# PH_074_isolated_SMD.net
KiCad netlist of a schematic drawn in EAGLE
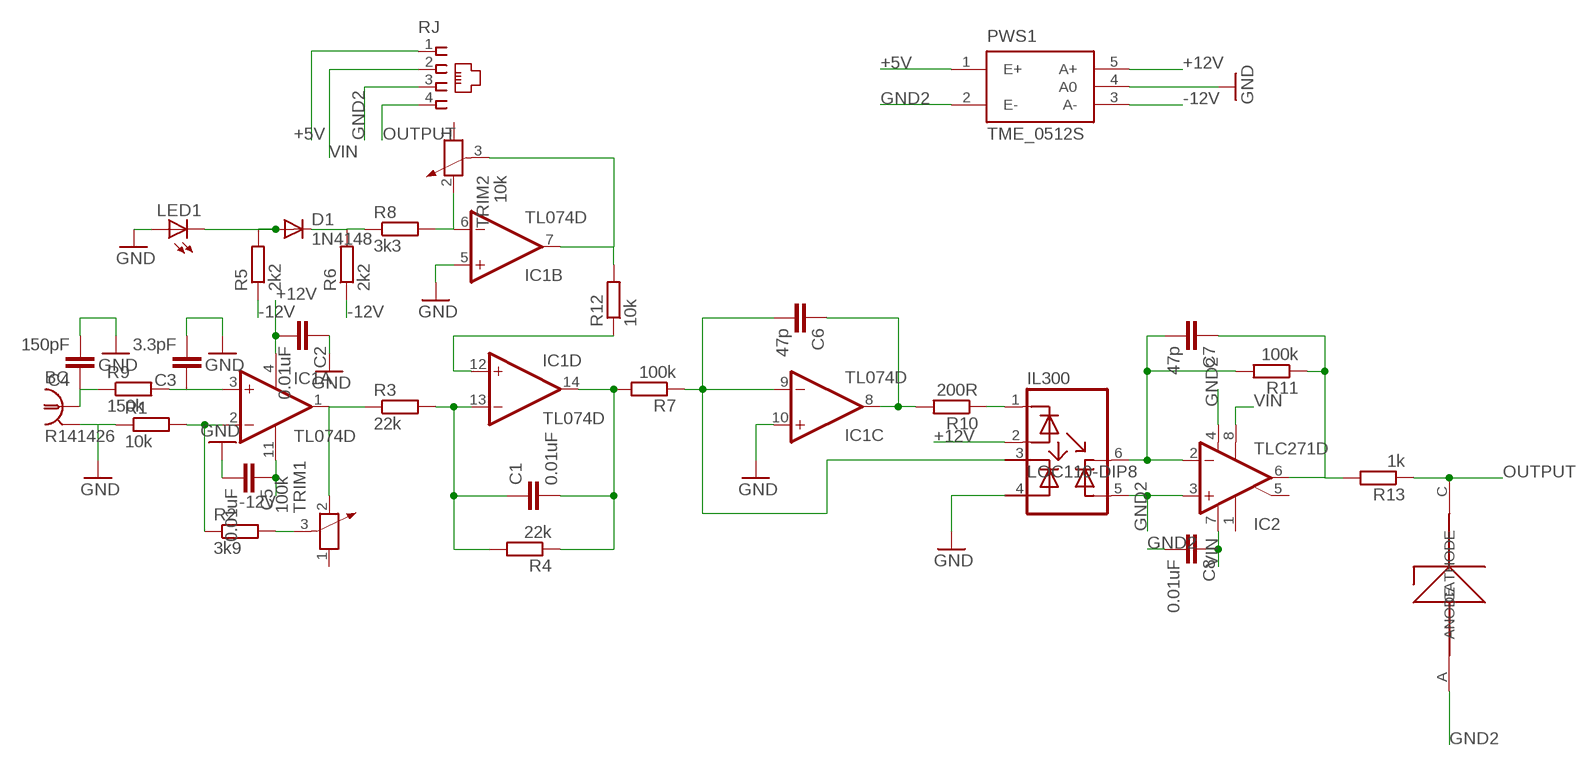
[diagram p0: schematic, sheet 1]

(export (version "E")
  (design (tool "Eeschema 10.0.6"))
  (components
    (comp (ref "BC")
      (value "R141426")
      (footprint "eagle-import:R141426")
      (fields (field (name "MF") "FARNELL") (field (name "MPN") "R141426161"))
      (libsource (lib "eagle-import") (part "R141426"))
    )
    (comp (ref "C1")
      (value "0.01uF")
      (footprint "eagle-import:C1206")
      (libsource (lib "eagle-import") (part "C-EUC1206"))
    )
    (comp (ref "C2")
      (value "0.01uF")
      (footprint "eagle-import:C1206")
      (libsource (lib "eagle-import") (part "C-EUC1206"))
    )
    (comp (ref "C3")
      (value "3.3pF")
      (footprint "eagle-import:C0805")
      (libsource (lib "eagle-import") (part "C-EUC0805"))
    )
    (comp (ref "C4")
      (value "150pF")
      (footprint "eagle-import:C0805")
      (libsource (lib "eagle-import") (part "C-EUC0805"))
    )
    (comp (ref "C5")
      (value "0.01uF")
      (footprint "eagle-import:C0805")
      (libsource (lib "eagle-import") (part "C-EUC0805"))
    )
    (comp (ref "C6")
      (value "47p")
      (footprint "eagle-import:C0805")
      (libsource (lib "eagle-import") (part "C-EUC0805"))
    )
    (comp (ref "C7")
      (value "47p")
      (footprint "eagle-import:C1206")
      (libsource (lib "eagle-import") (part "C-EUC1206"))
    )
    (comp (ref "C8")
      (value "0.01uF")
      (footprint "eagle-import:C0805")
      (libsource (lib "eagle-import") (part "C-EUC0805"))
    )
    (comp (ref "D1")
      (value "1N4148")
      (footprint "eagle-import:R1206W")
      (libsource (lib "eagle-import") (part "1N4148"))
    )
    (comp (ref "IC1")
      (value "TL074D")
      (footprint "eagle-import:SO14")
      (libsource (lib "eagle-import") (part "TL074D"))
    )
    (comp (ref "IC2")
      (value "TLC271D")
      (footprint "eagle-import:SO08")
      (libsource (lib "eagle-import") (part "TLC271D"))
    )
    (comp (ref "IL300")
      (value "LOC110-DIP8")
      (footprint "eagle-import:DIP8")
      (libsource (lib "eagle-import") (part "ILD621LOC110-DIP8"))
    )
    (comp (ref "LED1")
      (value "LED3MM")
      (footprint "eagle-import:LED3MM")
      (libsource (lib "eagle-import") (part "LED3MM"))
    )
    (comp (ref "PWS1")
      (value "TME_0512S")
      (footprint "eagle-import:TMEXXXXS")
      (fields (field (name "MPN") "TME 0512S"))
      (libsource (lib "eagle-import") (part "TME_S0512"))
    )
    (comp (ref "R1")
      (value "10k")
      (footprint "eagle-import:R1206W")
      (libsource (lib "eagle-import") (part "R-EU_R1206W"))
    )
    (comp (ref "R2")
      (value "3k9")
      (footprint "eagle-import:R1206W")
      (libsource (lib "eagle-import") (part "R-EU_R1206W"))
    )
    (comp (ref "R3")
      (value "22k")
      (footprint "eagle-import:R1206W")
      (libsource (lib "eagle-import") (part "R-EU_R1206W"))
    )
    (comp (ref "R4")
      (value "22k")
      (footprint "eagle-import:R1206W")
      (libsource (lib "eagle-import") (part "R-EU_R1206W"))
    )
    (comp (ref "R5")
      (value "2k2")
      (footprint "eagle-import:R1206W")
      (libsource (lib "eagle-import") (part "R-EU_R1206W"))
    )
    (comp (ref "R6")
      (value "2k2")
      (footprint "eagle-import:R1206W")
      (libsource (lib "eagle-import") (part "R-EU_R1206W"))
    )
    (comp (ref "R7")
      (value "100k")
      (footprint "eagle-import:R1206W")
      (libsource (lib "eagle-import") (part "R-EU_R1206W"))
    )
    (comp (ref "R8")
      (value "3k3")
      (footprint "eagle-import:R1206W")
      (libsource (lib "eagle-import") (part "R-EU_R1206W"))
    )
    (comp (ref "R9")
      (value "150k")
      (footprint "eagle-import:R0805W")
      (libsource (lib "eagle-import") (part "R-EU_R0805W"))
    )
    (comp (ref "R10")
      (value "200R")
      (footprint "eagle-import:R1206W")
      (libsource (lib "eagle-import") (part "R-EU_R1206W"))
    )
    (comp (ref "R11")
      (value "100k")
      (footprint "eagle-import:R1206W")
      (libsource (lib "eagle-import") (part "R-EU_R1206W"))
    )
    (comp (ref "R12")
      (value "10k")
      (footprint "eagle-import:R1206W")
      (libsource (lib "eagle-import") (part "R-EU_R1206W"))
    )
    (comp (ref "R13")
      (value "1k")
      (footprint "eagle-import:R1206W")
      (libsource (lib "eagle-import") (part "R-EU_R1206W"))
    )
    (comp (ref "RJ")
      (value "14867")
      (footprint "eagle-import:14867")
      (libsource (lib "eagle-import") (part "14867"))
    )
    (comp (ref "TRIM1")
      (value "100k")
      (footprint "eagle-import:PT-10")
      (libsource (lib "eagle-import") (part "POTENTIOMETER_PT-10"))
    )
    (comp (ref "TRIM2")
      (value "10k")
      (footprint "eagle-import:PT-10")
      (libsource (lib "eagle-import") (part "POTENTIOMETER_PT-10"))
    )
    (comp (ref "U$1")
      (value "ZENER")
      (footprint "eagle-import:SOD80-W")
      (libsource (lib "eagle-import") (part "ZENER"))
    )
  )
  (nets
    (net (code "1") (name "/+5V") (class "Default")
      (node (ref "PWS1") (pin "1") (pinfunction "E+_1") (pintype "input"))
      (node (ref "RJ") (pin "1") (pinfunction "1_1") (pintype "passive"))
    )
    (net (code "2") (name "/+12V") (class "Default")
      (node (ref "C2") (pin "2") (pinfunction "2_2") (pintype "passive"))
      (node (ref "IC1") (pin "4") (pinfunction "V+_4") (pintype "power_in"))
      (node (ref "IL300") (pin "2") (pinfunction "2_2") (pintype "passive"))
      (node (ref "PWS1") (pin "5") (pinfunction "A+_5") (pintype "output"))
    )
    (net (code "3") (name "/-12V") (class "Default")
      (node (ref "C5") (pin "1") (pinfunction "1_1") (pintype "passive"))
      (node (ref "IC1") (pin "11") (pinfunction "V-_11") (pintype "power_in"))
      (node (ref "PWS1") (pin "3") (pinfunction "A-_3") (pintype "output"))
      (node (ref "R5") (pin "1") (pinfunction "1_1") (pintype "passive"))
      (node (ref "R6") (pin "1") (pinfunction "1_1") (pintype "passive"))
    )
    (net (code "4") (name "/GND2") (class "Default")
      (node (ref "C8") (pin "2") (pinfunction "2_2") (pintype "passive"))
      (node (ref "IC2") (pin "3") (pinfunction "+IN_3") (pintype "input"))
      (node (ref "IC2") (pin "4") (pinfunction "V-_4") (pintype "power_in"))
      (node (ref "IL300") (pin "5") (pinfunction "5_5") (pintype "passive"))
      (node (ref "PWS1") (pin "2") (pinfunction "E-_2") (pintype "input"))
      (node (ref "RJ") (pin "3") (pinfunction "3_3") (pintype "passive"))
      (node (ref "U$1") (pin "A") (pinfunction "ANODE_A") (pintype "bidirectional"))
    )
    (net (code "5") (name "/OUTPUT") (class "Default")
      (node (ref "R13") (pin "1") (pinfunction "1_1") (pintype "passive"))
      (node (ref "RJ") (pin "4") (pinfunction "4_4") (pintype "passive"))
      (node (ref "U$1") (pin "C") (pinfunction "CATHODE_C") (pintype "bidirectional"))
    )
    (net (code "6") (name "/VIN") (class "Default")
      (node (ref "C8") (pin "1") (pinfunction "1_1") (pintype "passive"))
      (node (ref "IC2") (pin "7") (pinfunction "V+_7") (pintype "power_in"))
      (node (ref "IC2") (pin "8") (pinfunction "OPT_8") (pintype "passive"))
      (node (ref "RJ") (pin "2") (pinfunction "2_2") (pintype "passive"))
    )
    (net (code "7") (name "GND") (class "Default")
      (node (ref "BC") (pin "2") (pinfunction "GND_2") (pintype "power_in"))
      (node (ref "C2") (pin "1") (pinfunction "1_1") (pintype "passive"))
      (node (ref "C3") (pin "2") (pinfunction "2_2") (pintype "passive"))
      (node (ref "C4") (pin "2") (pinfunction "2_2") (pintype "passive"))
      (node (ref "C5") (pin "2") (pinfunction "2_2") (pintype "passive"))
      (node (ref "IC1") (pin "10") (pinfunction "+IN_10") (pintype "input"))
      (node (ref "IC1") (pin "5") (pinfunction "+IN_5") (pintype "input"))
      (node (ref "IL300") (pin "4") (pinfunction "4_4") (pintype "passive"))
      (node (ref "LED1") (pin "A") (pinfunction "A_A") (pintype "passive"))
      (node (ref "PWS1") (pin "4") (pinfunction "A0_4") (pintype "output"))
      (node (ref "R1") (pin "1") (pinfunction "1_1") (pintype "passive"))
    )
    (net (code "8") (name "Net-(BC-Pad1)") (class "Default")
      (node (ref "BC") (pin "1") (pinfunction "1_1") (pintype "passive"))
      (node (ref "C4") (pin "1") (pinfunction "1_1") (pintype "passive"))
      (node (ref "R9") (pin "1") (pinfunction "1_1") (pintype "passive"))
    )
    (net (code "9") (name "Net-(D1-A)") (class "Default")
      (node (ref "D1") (pin "1") (pinfunction "A_1") (pintype "passive"))
      (node (ref "LED1") (pin "K") (pinfunction "C_K") (pintype "passive"))
      (node (ref "R5") (pin "2") (pinfunction "2_2") (pintype "passive"))
    )
    (net (code "10") (name "Net-(D1-C)") (class "Default")
      (node (ref "D1") (pin "2") (pinfunction "C_2") (pintype "passive"))
      (node (ref "R6") (pin "2") (pinfunction "2_2") (pintype "passive"))
      (node (ref "R8") (pin "1") (pinfunction "1_1") (pintype "passive"))
    )
    (net (code "11") (name "Net-(IC1A-+IN)") (class "Default")
      (node (ref "C3") (pin "1") (pinfunction "1_1") (pintype "passive"))
      (node (ref "IC1") (pin "3") (pinfunction "+IN_3") (pintype "input"))
      (node (ref "R9") (pin "2") (pinfunction "2_2") (pintype "passive"))
    )
    (net (code "12") (name "Net-(IC1A--IN)") (class "Default")
      (node (ref "IC1") (pin "2") (pinfunction "-IN_2") (pintype "input"))
      (node (ref "R1") (pin "2") (pinfunction "2_2") (pintype "passive"))
      (node (ref "R2") (pin "1") (pinfunction "1_1") (pintype "passive"))
    )
    (net (code "13") (name "Net-(IC1A-OUT)") (class "Default")
      (node (ref "IC1") (pin "1") (pinfunction "OUT_1") (pintype "output"))
      (node (ref "R3") (pin "1") (pinfunction "1_1") (pintype "passive"))
      (node (ref "TRIM1") (pin "2") (pinfunction "2_2") (pintype "passive"))
    )
    (net (code "14") (name "Net-(IC1B--IN)") (class "Default")
      (node (ref "IC1") (pin "6") (pinfunction "-IN_6") (pintype "input"))
      (node (ref "R8") (pin "2") (pinfunction "2_2") (pintype "passive"))
      (node (ref "TRIM2") (pin "2") (pinfunction "2_2") (pintype "passive"))
    )
    (net (code "15") (name "Net-(IC1B-OUT)") (class "Default")
      (node (ref "IC1") (pin "7") (pinfunction "OUT_7") (pintype "output"))
      (node (ref "R12") (pin "2") (pinfunction "2_2") (pintype "passive"))
      (node (ref "TRIM2") (pin "3") (pinfunction "3_3") (pintype "passive"))
    )
    (net (code "16") (name "Net-(IC1C--IN)") (class "Default")
      (node (ref "C6") (pin "2") (pinfunction "2_2") (pintype "passive"))
      (node (ref "IC1") (pin "9") (pinfunction "-IN_9") (pintype "input"))
      (node (ref "IL300") (pin "3") (pinfunction "3_3") (pintype "passive"))
      (node (ref "R7") (pin "1") (pinfunction "1_1") (pintype "passive"))
    )
    (net (code "17") (name "Net-(IC1C-OUT)") (class "Default")
      (node (ref "C6") (pin "1") (pinfunction "1_1") (pintype "passive"))
      (node (ref "IC1") (pin "8") (pinfunction "OUT_8") (pintype "output"))
      (node (ref "R10") (pin "2") (pinfunction "2_2") (pintype "passive"))
    )
    (net (code "18") (name "Net-(IC1D-+IN)") (class "Default")
      (node (ref "IC1") (pin "12") (pinfunction "+IN_12") (pintype "input"))
      (node (ref "R12") (pin "1") (pinfunction "1_1") (pintype "passive"))
    )
    (net (code "19") (name "Net-(IC1D--IN)") (class "Default")
      (node (ref "C1") (pin "1") (pinfunction "1_1") (pintype "passive"))
      (node (ref "IC1") (pin "13") (pinfunction "-IN_13") (pintype "input"))
      (node (ref "R3") (pin "2") (pinfunction "2_2") (pintype "passive"))
      (node (ref "R4") (pin "2") (pinfunction "2_2") (pintype "passive"))
    )
    (net (code "20") (name "Net-(IC1D-OUT)") (class "Default")
      (node (ref "C1") (pin "2") (pinfunction "2_2") (pintype "passive"))
      (node (ref "IC1") (pin "14") (pinfunction "OUT_14") (pintype "output"))
      (node (ref "R4") (pin "1") (pinfunction "1_1") (pintype "passive"))
      (node (ref "R7") (pin "2") (pinfunction "2_2") (pintype "passive"))
    )
    (net (code "21") (name "Net-(IC2--IN)") (class "Default")
      (node (ref "C7") (pin "2") (pinfunction "2_2") (pintype "passive"))
      (node (ref "IC2") (pin "2") (pinfunction "-IN_2") (pintype "input"))
      (node (ref "IL300") (pin "6") (pinfunction "6_6") (pintype "passive"))
      (node (ref "R11") (pin "2") (pinfunction "2_2") (pintype "passive"))
    )
    (net (code "22") (name "Net-(IC2-OUT)") (class "Default")
      (node (ref "C7") (pin "1") (pinfunction "1_1") (pintype "passive"))
      (node (ref "IC2") (pin "6") (pinfunction "OUT_6") (pintype "output"))
      (node (ref "R11") (pin "1") (pinfunction "1_1") (pintype "passive"))
      (node (ref "R13") (pin "2") (pinfunction "2_2") (pintype "passive"))
    )
    (net (code "23") (name "Net-(IL300-Pad1)") (class "Default")
      (node (ref "IL300") (pin "1") (pinfunction "1_1") (pintype "passive"))
      (node (ref "R10") (pin "1") (pinfunction "1_1") (pintype "passive"))
    )
    (net (code "24") (name "Net-(R2-Pad2)") (class "Default")
      (node (ref "R2") (pin "2") (pinfunction "2_2") (pintype "passive"))
      (node (ref "TRIM1") (pin "3") (pinfunction "3_3") (pintype "passive"))
    )
    (net (code "25") (name "unconnected-(IC2-ON1-Pad1)") (class "Default")
      (node (ref "IC2") (pin "1") (pinfunction "ON1_1") (pintype "passive"))
    )
    (net (code "26") (name "unconnected-(IC2-ON2-Pad5)") (class "Default")
      (node (ref "IC2") (pin "5") (pinfunction "ON2_5") (pintype "passive"))
    )
    (net (code "27") (name "unconnected-(TRIM1-Pad1)") (class "Default")
      (node (ref "TRIM1") (pin "1") (pinfunction "1_1") (pintype "passive"))
    )
    (net (code "28") (name "unconnected-(TRIM2-Pad1)") (class "Default")
      (node (ref "TRIM2") (pin "1") (pinfunction "1_1") (pintype "passive"))
    )
  )
)
